# LED.net
KiCad netlist of a schematic drawn in EAGLE
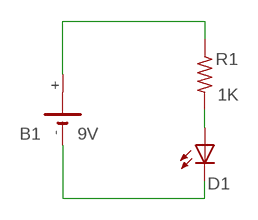
[diagram p0: schematic, sheet 1]

(export (version "E")
  (design (tool "Eeschema 10.0.6"))
  (components
    (comp (ref "B1")
      (value "9V")
      (footprint "eagle-import:CR2032H")
      (libsource (lib "eagle-import") (part "CR2032H"))
    )
    (comp (ref "D1")
      (value "LED5MM")
      (footprint "eagle-import:LED5MM")
      (libsource (lib "eagle-import") (part "LED5MM"))
    )
    (comp (ref "R1")
      (value "1K")
      (footprint "eagle-import:0309_12")
      (libsource (lib "eagle-import") (part "R-US_0309/12"))
    )
  )
  (nets
    (net (code "1") (name "Net-(B1-Pad+)") (class "Default")
      (node (ref "B1") (pin "+") (pinfunction "+_+") (pintype "passive"))
      (node (ref "R1") (pin "1") (pinfunction "1_1") (pintype "passive"))
    )
    (net (code "2") (name "Net-(D1-C)") (class "Default")
      (node (ref "B1") (pin "-") (pinfunction "-_-") (pintype "passive"))
      (node (ref "D1") (pin "K") (pinfunction "C_K") (pintype "passive"))
    )
    (net (code "3") (name "Net-(D1-PadA)") (class "Default")
      (node (ref "D1") (pin "A") (pinfunction "A_A") (pintype "passive"))
      (node (ref "R1") (pin "2") (pinfunction "2_2") (pintype "passive"))
    )
    (net (code "4") (name "unconnected-(B1-+-Pad+@1)") (class "Default")
      (node (ref "B1") (pin "+@1") (pinfunction "+_+@1") (pintype "passive"))
    )
  )
)
